# fox_circuit.net
KiCad netlist of a schematic drawn in EAGLE
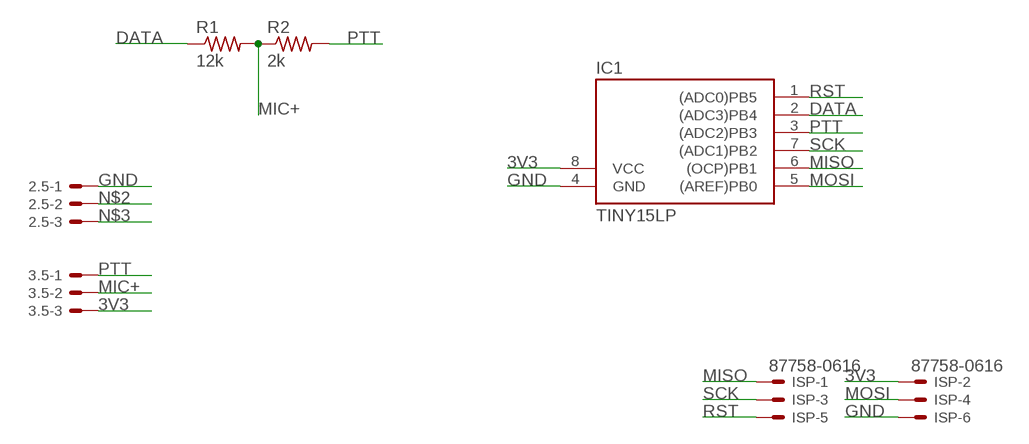
[diagram p0: schematic, sheet 1]

(export (version "E")
  (design (tool "Eeschema 10.0.6"))
  (components
    (comp (ref "2.5")
      (value "KK-156-3")
      (footprint "eagle-import:KK-156-3")
      (libsource (lib "eagle-import") (part "KK-156-3"))
    )
    (comp (ref "3.5")
      (value "KK-156-3")
      (footprint "eagle-import:KK-156-3")
      (libsource (lib "eagle-import") (part "KK-156-3"))
    )
    (comp (ref "IC1")
      (value "TINY15LP")
      (footprint "eagle-import:DIL08")
      (libsource (lib "eagle-import") (part "TINY15LP"))
    )
    (comp (ref "ISP")
      (value "87758-0616")
      (footprint "eagle-import:87758-0616")
      (libsource (lib "eagle-import") (part "87758-0616"))
    )
    (comp (ref "R1")
      (value "12k")
      (footprint "eagle-import:RDH_15")
      (libsource (lib "eagle-import") (part "R-US_RDH/15"))
    )
    (comp (ref "R2")
      (value "2k")
      (footprint "eagle-import:RDH_15")
      (libsource (lib "eagle-import") (part "R-US_RDH/15"))
    )
  )
  (nets
    (net (code "1") (name "/3V3") (class "Default")
      (node (ref "3.5") (pin "3") (pinfunction "S_3") (pintype "passive"))
      (node (ref "IC1") (pin "8") (pinfunction "VCC_8") (pintype "power_in"))
      (node (ref "ISP") (pin "2") (pinfunction "S_2") (pintype "passive"))
    )
    (net (code "2") (name "/DATA") (class "Default")
      (node (ref "IC1") (pin "2") (pinfunction "(ADC3)PB4_2") (pintype "bidirectional"))
      (node (ref "R1") (pin "1") (pinfunction "1_1") (pintype "passive"))
    )
    (net (code "3") (name "/GND") (class "Default")
      (node (ref "2.5") (pin "1") (pinfunction "S_1") (pintype "passive"))
      (node (ref "IC1") (pin "4") (pinfunction "GND_4") (pintype "power_in"))
      (node (ref "ISP") (pin "6") (pinfunction "S_6") (pintype "passive"))
    )
    (net (code "4") (name "/MIC+") (class "Default")
      (node (ref "3.5") (pin "2") (pinfunction "S_2") (pintype "passive"))
      (node (ref "R1") (pin "2") (pinfunction "2_2") (pintype "passive"))
      (node (ref "R2") (pin "1") (pinfunction "1_1") (pintype "passive"))
    )
    (net (code "5") (name "/MISO") (class "Default")
      (node (ref "IC1") (pin "6") (pinfunction "(OCP)PB1_6") (pintype "bidirectional"))
      (node (ref "ISP") (pin "1") (pinfunction "S_1") (pintype "passive"))
    )
    (net (code "6") (name "/MOSI") (class "Default")
      (node (ref "IC1") (pin "5") (pinfunction "(AREF)PB0_5") (pintype "bidirectional"))
      (node (ref "ISP") (pin "4") (pinfunction "S_4") (pintype "passive"))
    )
    (net (code "7") (name "/N$2") (class "Default")
      (node (ref "2.5") (pin "2") (pinfunction "S_2") (pintype "passive"))
    )
    (net (code "8") (name "/N$3") (class "Default")
      (node (ref "2.5") (pin "3") (pinfunction "S_3") (pintype "passive"))
    )
    (net (code "9") (name "/PTT") (class "Default")
      (node (ref "3.5") (pin "1") (pinfunction "S_1") (pintype "passive"))
      (node (ref "IC1") (pin "3") (pinfunction "(ADC2)PB3_3") (pintype "bidirectional"))
      (node (ref "R2") (pin "2") (pinfunction "2_2") (pintype "passive"))
    )
    (net (code "10") (name "/RST") (class "Default")
      (node (ref "IC1") (pin "1") (pinfunction "(ADC0)PB5_1") (pintype "bidirectional"))
      (node (ref "ISP") (pin "5") (pinfunction "S_5") (pintype "passive"))
    )
    (net (code "11") (name "/SCK") (class "Default")
      (node (ref "IC1") (pin "7") (pinfunction "(ADC1)PB2_7") (pintype "bidirectional"))
      (node (ref "ISP") (pin "3") (pinfunction "S_3") (pintype "passive"))
    )
  )
)
